# Sheet1.net
KiCad netlist of a schematic drawn in EasyEDA
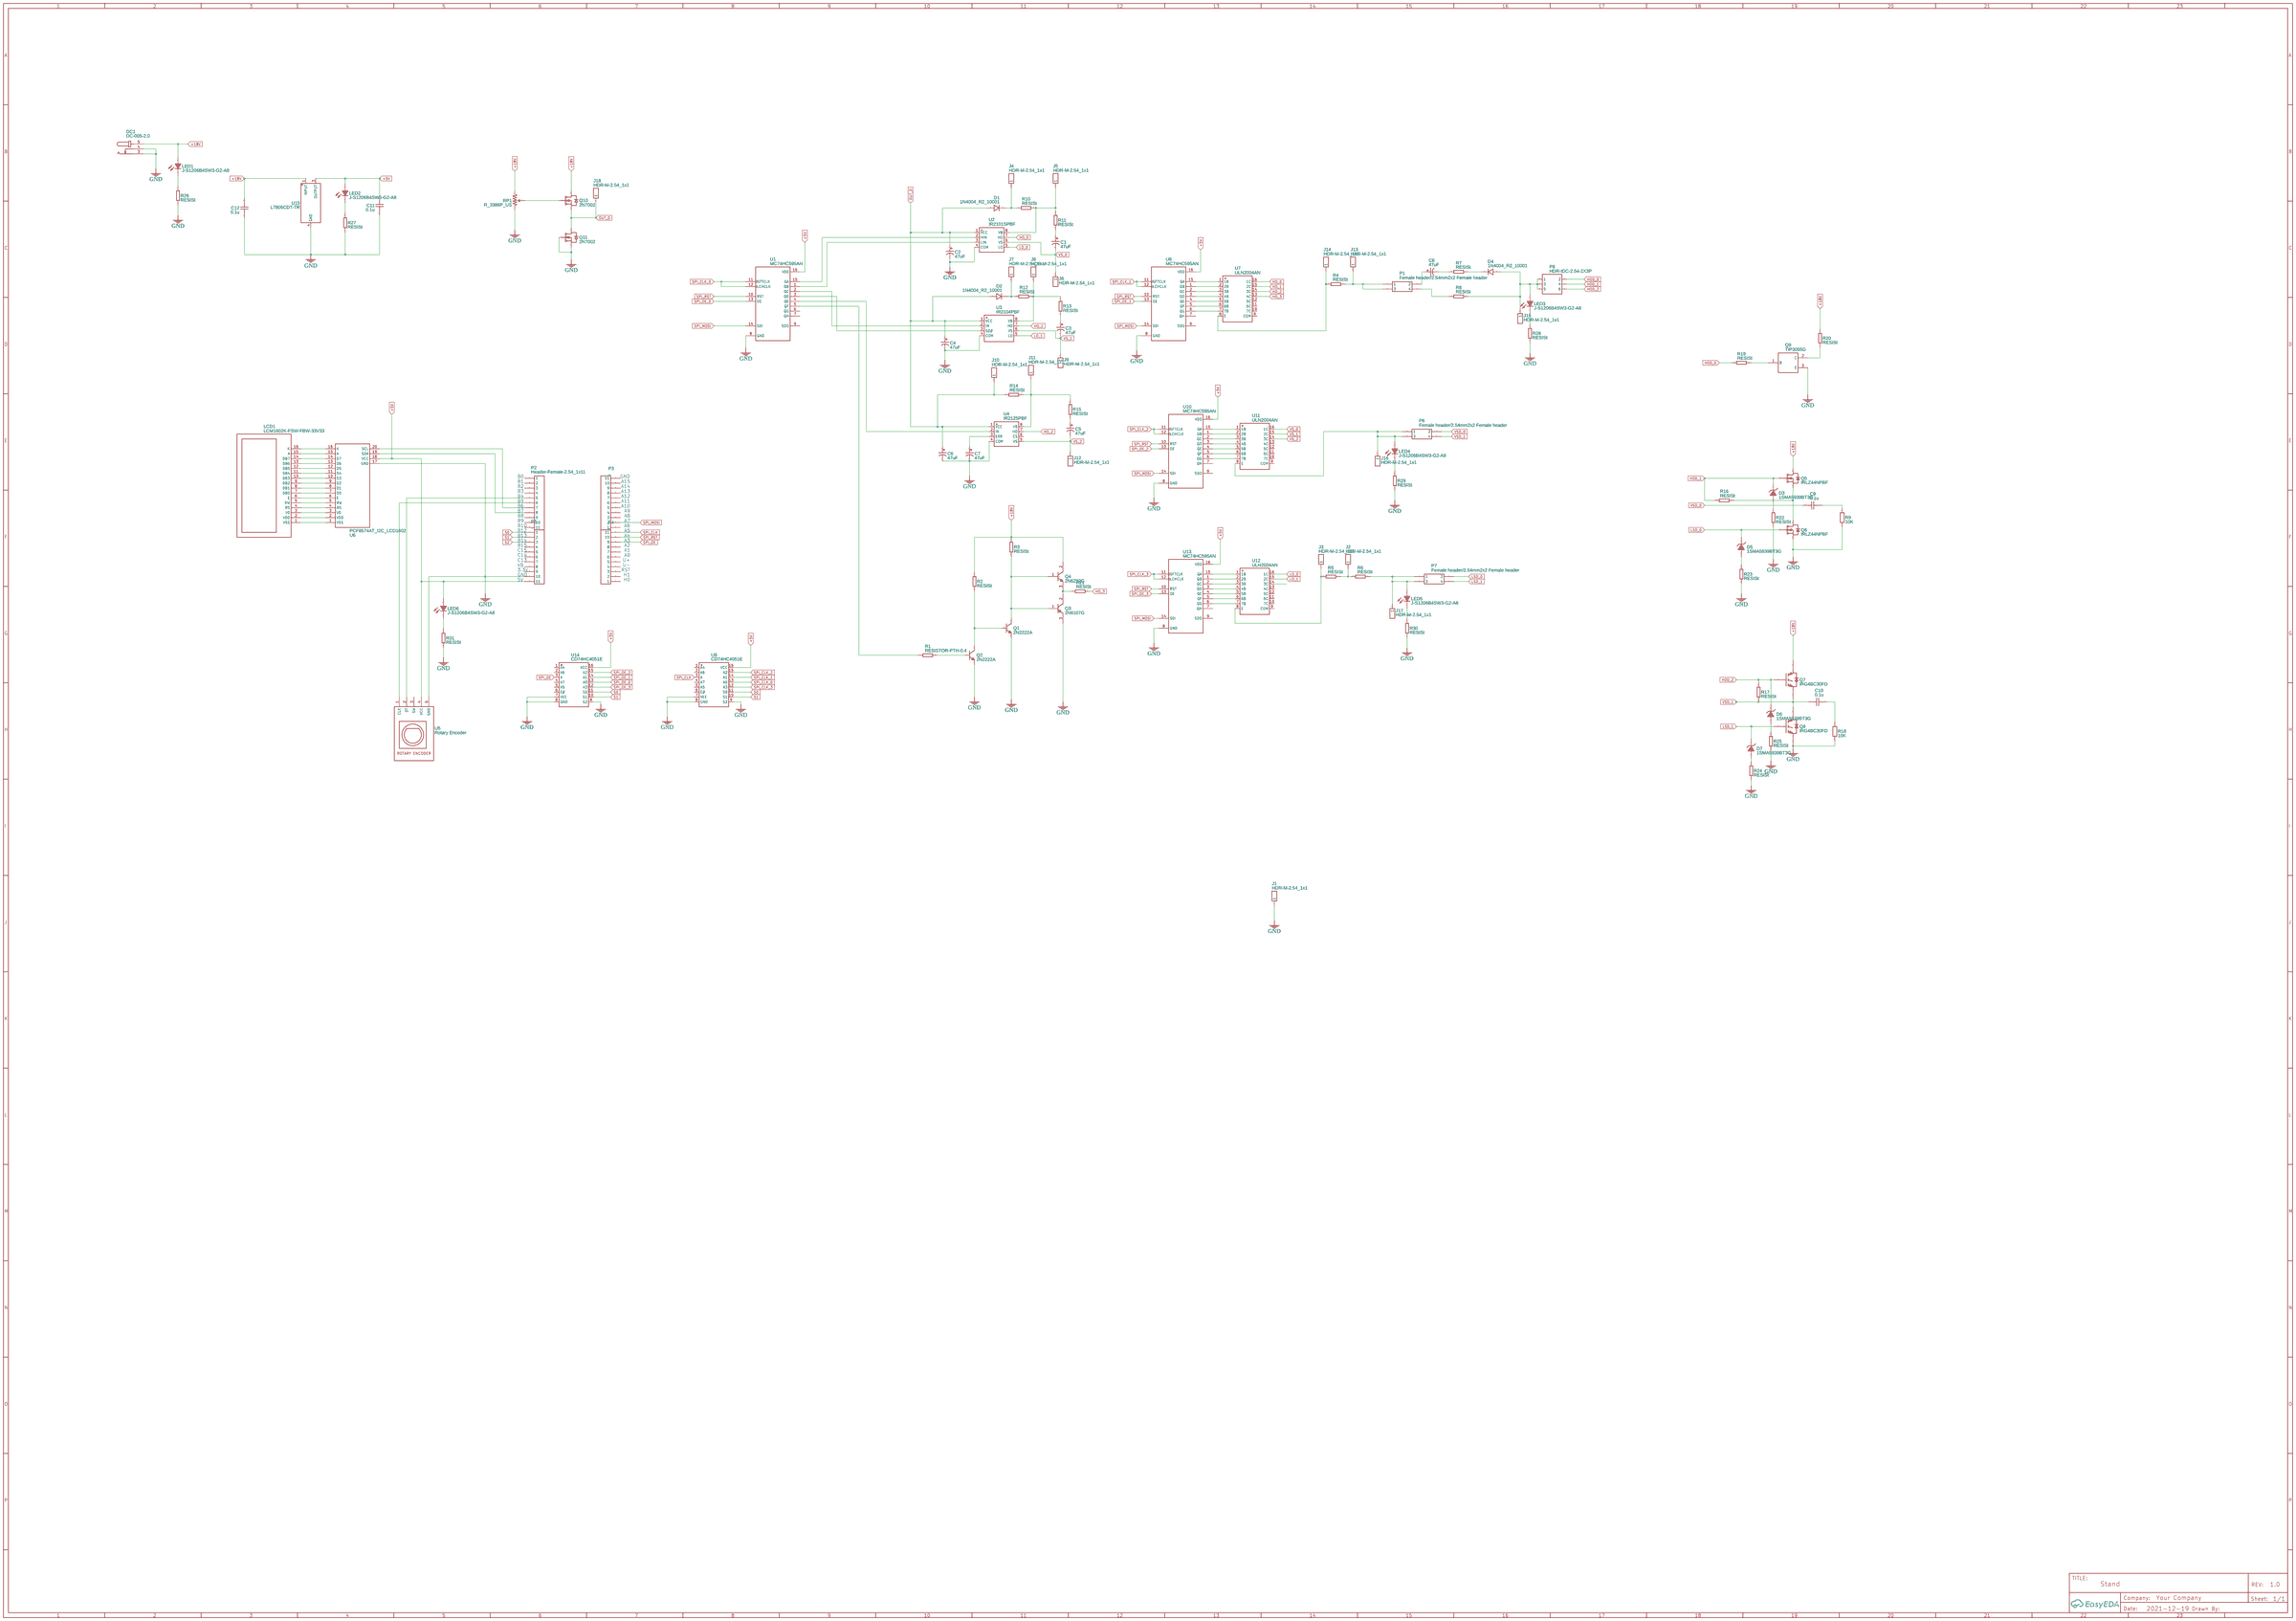
[diagram p0: schematic sheet]

(export (version "E")
  (design (tool "Eeschema 10.0.6"))
  (components
    (comp (ref "C1")
      (value "47uF")
      (fields
        (field (name "BOM_Manufacturer Part") "RD1J476M6L011PC380")
        (field (name "BOM_Supplier Part") "C238012")
      )
      (libsource (lib "") (part "RD1J476M6L011PC380"))
    )
    (comp (ref "C2")
      (value "47uF")
      (fields
        (field (name "BOM_Manufacturer Part") "RD1J476M6L011PC380")
        (field (name "BOM_Supplier Part") "C238012")
      )
      (libsource (lib "") (part "RD1J476M6L011PC380"))
    )
    (comp (ref "C3")
      (value "47uF")
      (fields
        (field (name "BOM_Manufacturer Part") "RD1J476M6L011PC380")
        (field (name "BOM_Supplier Part") "C238012")
      )
      (libsource (lib "") (part "RD1J476M6L011PC380"))
    )
    (comp (ref "C4")
      (value "47uF")
      (fields
        (field (name "BOM_Manufacturer Part") "RD1J476M6L011PC380")
        (field (name "BOM_Supplier Part") "C238012")
      )
      (libsource (lib "") (part "RD1J476M6L011PC380"))
    )
    (comp (ref "C5")
      (value "47uF")
      (fields
        (field (name "BOM_Manufacturer Part") "RD1J476M6L011PC380")
        (field (name "BOM_Supplier Part") "C238012")
      )
      (libsource (lib "") (part "RD1J476M6L011PC380"))
    )
    (comp (ref "C6")
      (value "47uF")
      (fields
        (field (name "BOM_Manufacturer Part") "RD1J476M6L011PC380")
        (field (name "BOM_Supplier Part") "C238012")
      )
      (libsource (lib "") (part "RD1J476M6L011PC380"))
    )
    (comp (ref "C7")
      (value "47uF")
      (fields
        (field (name "BOM_Manufacturer Part") "RD1J476M6L011PC380")
        (field (name "BOM_Supplier Part") "C238012")
      )
      (libsource (lib "") (part "RD1J476M6L011PC380"))
    )
    (comp (ref "C8")
      (value "47uF")
      (fields
        (field (name "BOM_Manufacturer Part") "RD1J476M6L011PC380")
        (field (name "BOM_Supplier Part") "C238012")
      )
      (libsource (lib "") (part "RD1J476M6L011PC380_1"))
    )
    (comp (ref "C9") (value "0.1u") (libsource (lib "") (part "C_0603_US")))
    (comp (ref "C10") (value "0.1u") (libsource (lib "") (part "C_0603_US")))
    (comp (ref "C11") (value "0.1u") (libsource (lib "") (part "C_0603_US_1")))
    (comp (ref "C12") (value "0.1u") (libsource (lib "") (part "C_0603_US_1")))
    (comp (ref "D1")
      (value "1N4004_R2_10001")
      (fields (field (name "BOM_Supplier Part") "C391322"))
      (libsource (lib "") (part "1N4004_R2_10001_1"))
    )
    (comp (ref "D2")
      (value "1N4004_R2_10001")
      (fields (field (name "BOM_Supplier Part") "C391322"))
      (libsource (lib "") (part "1N4004_R2_10001_1"))
    )
    (comp (ref "D3")
      (value "1SMA5939BT3G")
      (fields (field (name "BOM_Supplier Part") "C238874"))
      (libsource (lib "") (part "1SMA5939BT3G"))
    )
    (comp (ref "D4")
      (value "1N4004_R2_10001")
      (fields (field (name "BOM_Supplier Part") "C391322"))
      (libsource (lib "") (part "1N4004_R2_10001"))
    )
    (comp (ref "D5")
      (value "1SMA5939BT3G")
      (fields (field (name "BOM_Supplier Part") "C238874"))
      (libsource (lib "") (part "1SMA5939BT3G"))
    )
    (comp (ref "D6")
      (value "1SMA5939BT3G")
      (fields (field (name "BOM_Supplier Part") "C238874"))
      (libsource (lib "") (part "1SMA5939BT3G"))
    )
    (comp (ref "D7")
      (value "1SMA5939BT3G")
      (fields (field (name "BOM_Supplier Part") "C238874"))
      (libsource (lib "") (part "1SMA5939BT3G"))
    )
    (comp (ref "DC1")
      (value "DC-005-2.0")
      (fields (field (name "BOM_Supplier Part") "C521451"))
      (libsource (lib "") (part "DC-005-2.0"))
    )
    (comp (ref "J1")
      (value "HDR-M-2.54_1x1")
      (fields (field (name "BOM_Supplier Part") "C81276"))
      (libsource (lib "") (part "HDR-M-2.54_1x1"))
    )
    (comp (ref "J2")
      (value "HDR-M-2.54_1x1")
      (fields (field (name "BOM_Supplier Part") "C81276"))
      (libsource (lib "") (part "HDR-M-2.54_1x1"))
    )
    (comp (ref "J3")
      (value "HDR-M-2.54_1x1")
      (fields (field (name "BOM_Supplier Part") "C81276"))
      (libsource (lib "") (part "HDR-M-2.54_1x1"))
    )
    (comp (ref "J4")
      (value "HDR-M-2.54_1x1")
      (fields (field (name "BOM_Supplier Part") "C81276"))
      (libsource (lib "") (part "HDR-M-2.54_1x1"))
    )
    (comp (ref "J5")
      (value "HDR-M-2.54_1x1")
      (fields (field (name "BOM_Supplier Part") "C81276"))
      (libsource (lib "") (part "HDR-M-2.54_1x1"))
    )
    (comp (ref "J6")
      (value "HDR-M-2.54_1x1")
      (fields (field (name "BOM_Supplier Part") "C81276"))
      (libsource (lib "") (part "HDR-M-2.54_1x1_1"))
    )
    (comp (ref "J7")
      (value "HDR-M-2.54_1x1")
      (fields (field (name "BOM_Supplier Part") "C81276"))
      (libsource (lib "") (part "HDR-M-2.54_1x1"))
    )
    (comp (ref "J8")
      (value "HDR-M-2.54_1x1")
      (fields (field (name "BOM_Supplier Part") "C81276"))
      (libsource (lib "") (part "HDR-M-2.54_1x1"))
    )
    (comp (ref "J9")
      (value "HDR-M-2.54_1x1")
      (fields (field (name "BOM_Supplier Part") "C81276"))
      (libsource (lib "") (part "HDR-M-2.54_1x1_1"))
    )
    (comp (ref "J10")
      (value "HDR-M-2.54_1x1")
      (fields (field (name "BOM_Supplier Part") "C81276"))
      (libsource (lib "") (part "HDR-M-2.54_1x1"))
    )
    (comp (ref "J11")
      (value "HDR-M-2.54_1x1")
      (fields (field (name "BOM_Supplier Part") "C81276"))
      (libsource (lib "") (part "HDR-M-2.54_1x1"))
    )
    (comp (ref "J12")
      (value "HDR-M-2.54_1x1")
      (fields (field (name "BOM_Supplier Part") "C81276"))
      (libsource (lib "") (part "HDR-M-2.54_1x1_1"))
    )
    (comp (ref "J13")
      (value "HDR-M-2.54_1x1")
      (fields (field (name "BOM_Supplier Part") "C81276"))
      (libsource (lib "") (part "HDR-M-2.54_1x1"))
    )
    (comp (ref "J14")
      (value "HDR-M-2.54_1x1")
      (fields (field (name "BOM_Supplier Part") "C81276"))
      (libsource (lib "") (part "HDR-M-2.54_1x1"))
    )
    (comp (ref "J15")
      (value "HDR-M-2.54_1x1")
      (fields (field (name "BOM_Supplier Part") "C81276"))
      (libsource (lib "") (part "HDR-M-2.54_1x1_1"))
    )
    (comp (ref "J16")
      (value "HDR-M-2.54_1x1")
      (fields (field (name "BOM_Supplier Part") "C81276"))
      (libsource (lib "") (part "HDR-M-2.54_1x1_1"))
    )
    (comp (ref "J17")
      (value "HDR-M-2.54_1x1")
      (fields (field (name "BOM_Supplier Part") "C81276"))
      (libsource (lib "") (part "HDR-M-2.54_1x1_1"))
    )
    (comp (ref "J18")
      (value "HDR-M-2.54_1x1")
      (fields (field (name "BOM_Supplier Part") "C81276"))
      (libsource (lib "") (part "HDR-M-2.54_1x1"))
    )
    (comp (ref "LCD1")
      (value "LCM1602K-FSW-FBW-33V33")
      (fields (field (name "BOM_Supplier Part") "C83271"))
      (libsource (lib "") (part "LCM1602K-FSW-FBW-33V33"))
    )
    (comp (ref "LED1")
      (value "J-S1206B4SW3-G2-A8")
      (fields (field (name "BOM_Supplier Part") "C2917491"))
      (libsource (lib "") (part "J-S1206B4SW3-G2-A8"))
    )
    (comp (ref "LED2")
      (value "J-S1206B4SW3-G2-A8")
      (fields (field (name "BOM_Supplier Part") "C2917491"))
      (libsource (lib "") (part "J-S1206B4SW3-G2-A8"))
    )
    (comp (ref "LED3")
      (value "J-S1206B4SW3-G2-A8")
      (fields (field (name "BOM_Supplier Part") "C2917491"))
      (libsource (lib "") (part "J-S1206B4SW3-G2-A8"))
    )
    (comp (ref "LED4")
      (value "J-S1206B4SW3-G2-A8")
      (fields (field (name "BOM_Supplier Part") "C2917491"))
      (libsource (lib "") (part "J-S1206B4SW3-G2-A8"))
    )
    (comp (ref "LED5")
      (value "J-S1206B4SW3-G2-A8")
      (fields (field (name "BOM_Supplier Part") "C2917491"))
      (libsource (lib "") (part "J-S1206B4SW3-G2-A8"))
    )
    (comp (ref "LED6")
      (value "J-S1206B4SW3-G2-A8")
      (fields (field (name "BOM_Supplier Part") "C2917491"))
      (libsource (lib "") (part "J-S1206B4SW3-G2-A8"))
    )
    (comp (ref "P1")
      (value "Female header/2.54mm2x2 Female header")
      (fields (field (name "BOM_Supplier Part") "undefined"))
      (libsource (lib "") (part "Female header/2.54mm2x2 Female header"))
    )
    (comp (ref "P2")
      (value "Header-Female-2.54_1x11")
      (fields
        (field (name "BOM_Manufacturer Part") "Header-Female-2.54_1x10")
        (field (name "BOM_Supplier Part") "undefined")
      )
      (libsource (lib "") (part "Header-Female-2.54_1x11"))
    )
    (comp (ref "P3")
      (value "_")
      (fields
        (field (name "BOM_Manufacturer Part") "Header-Female-2.54_1x10")
        (field (name "BOM_Supplier Part") "undefined")
      )
      (libsource (lib "") (part "Header-Female-2.54_1x11_1"))
    )
    (comp (ref "P4")
      (value "_")
      (fields
        (field (name "BOM_Manufacturer Part") "Header-Female-2.54_1x10")
        (field (name "BOM_Supplier Part") "undefined")
      )
      (libsource (lib "") (part "Header-Female-2.54_1x11_1"))
    )
    (comp (ref "P5")
      (value "_")
      (fields
        (field (name "BOM_Manufacturer Part") "Header-Female-2.54_1x10")
        (field (name "BOM_Supplier Part") "undefined")
      )
      (libsource (lib "") (part "Header-Female-2.54_1x11"))
    )
    (comp (ref "P6")
      (value "Female header/2.54mm2x2 Female header")
      (fields (field (name "BOM_Supplier Part") "undefined"))
      (libsource (lib "") (part "Female header/2.54mm2x2 Female header"))
    )
    (comp (ref "P7")
      (value "Female header/2.54mm2x2 Female header")
      (fields (field (name "BOM_Supplier Part") "undefined"))
      (libsource (lib "") (part "Female header/2.54mm2x2 Female header"))
    )
    (comp (ref "P8")
      (value "HDR-IDC-2.54-2X3P")
      (fields
        (field (name "BOM_Manufacturer Part") "2X3 2.54mm IDC Box")
        (field (name "BOM_Supplier Part") "C11214")
      )
      (libsource (lib "") (part "HDR-IDC-2.54-2X3P"))
    )
    (comp (ref "Q1")
      (value "2N2222A")
      (fields (field (name "BOM_Supplier Part") "C358533"))
      (libsource (lib "") (part "2N2222A"))
    )
    (comp (ref "Q2")
      (value "2N2222A")
      (fields (field (name "BOM_Supplier Part") "C358533"))
      (libsource (lib "") (part "2N2222A"))
    )
    (comp (ref "Q3") (value "2N6107G") (libsource (lib "") (part "2N6107G")))
    (comp (ref "Q4") (value "2N6292G") (libsource (lib "") (part "2N6292G")))
    (comp (ref "Q5")
      (value "IRLZ44NPBF")
      (fields (field (name "BOM_Supplier Part") "C38774"))
      (libsource (lib "") (part "IRLZ44NPBF"))
    )
    (comp (ref "Q6")
      (value "IRLZ44NPBF")
      (fields (field (name "BOM_Supplier Part") "C38774"))
      (libsource (lib "") (part "IRLZ44NPBF"))
    )
    (comp (ref "Q7") (value "IRG4BC30FD") (libsource (lib "") (part "IRG4BC30FD")))
    (comp (ref "Q8") (value "IRG4BC30FD") (libsource (lib "") (part "IRG4BC30FD")))
    (comp (ref "Q9") (value "TIP3055G") (libsource (lib "") (part "TIP3055G")))
    (comp (ref "Q10")
      (value "2N7002")
      (fields (field (name "BOM_Manufacturer Part") "2N7002,215") (field (name "BOM_Supplier Part") "C65189"))
      (libsource (lib "") (part "2N7002"))
    )
    (comp (ref "Q11")
      (value "2N7002")
      (fields (field (name "BOM_Manufacturer Part") "2N7002,215") (field (name "BOM_Supplier Part") "C65189"))
      (libsource (lib "") (part "2N7002"))
    )
    (comp (ref "R1") (value "RESISTOR-PTH-0.4") (libsource (lib "") (part "RESISTOR-PTH-0.4_2")))
    (comp (ref "R2") (value "RESISt") (libsource (lib "") (part "RESISTOR-PTH-0.4")))
    (comp (ref "R3") (value "RESISt") (libsource (lib "") (part "RESISTOR-PTH-0.4")))
    (comp (ref "R4") (value "RESISt") (libsource (lib "") (part "RESISTOR-PTH-0.4_3")))
    (comp (ref "R5") (value "RESISt") (libsource (lib "") (part "RESISTOR-PTH-0.4_3")))
    (comp (ref "R6") (value "RESISt") (libsource (lib "") (part "RESISTOR-PTH-0.4_3")))
    (comp (ref "R7") (value "RESISt") (libsource (lib "") (part "RESISTOR-PTH-0.4_3")))
    (comp (ref "R8") (value "RESISt") (libsource (lib "") (part "RESISTOR-PTH-0.4_3")))
    (comp (ref "R9")
      (value "10K")
      (fields
        (field (name "BOM_Manufacturer Part") "EWWR0010J10K0T9")
        (field (name "BOM_Supplier Part") "C349083")
      )
      (libsource (lib "") (part "EWWR0010J10K0T9"))
    )
    (comp (ref "R10") (value "RESISt") (libsource (lib "") (part "RESISTOR-PTH-0.4_2")))
    (comp (ref "R11") (value "RESISt") (libsource (lib "") (part "RESISTOR-PTH-0.4")))
    (comp (ref "R12") (value "RESISt") (libsource (lib "") (part "RESISTOR-PTH-0.4_2")))
    (comp (ref "R13") (value "RESISt") (libsource (lib "") (part "RESISTOR-PTH-0.4_1")))
    (comp (ref "R14") (value "RESISt") (libsource (lib "") (part "RESISTOR-PTH-0.4_2")))
    (comp (ref "R15") (value "RESISt") (libsource (lib "") (part "RESISTOR-PTH-0.4_1")))
    (comp (ref "R16") (value "RESISt") (libsource (lib "") (part "RESISTOR-PTH-0.4_3")))
    (comp (ref "R17") (value "RESISt") (libsource (lib "") (part "RESISTOR-PTH-0.4_1")))
    (comp (ref "R18")
      (value "10K")
      (fields
        (field (name "BOM_Manufacturer Part") "EWWR0010J10K0T9")
        (field (name "BOM_Supplier Part") "C349083")
      )
      (libsource (lib "") (part "EWWR0010J10K0T9"))
    )
    (comp (ref "R19") (value "RESISt") (libsource (lib "") (part "RESISTOR-PTH-0.4_3")))
    (comp (ref "R20") (value "RESISt") (libsource (lib "") (part "RESISTOR-PTH-0.4_1")))
    (comp (ref "R21") (value "RESISt") (libsource (lib "") (part "RESISTOR-PTH-0.4_2")))
    (comp (ref "R22") (value "RESISt") (libsource (lib "") (part "RESISTOR-PTH-0.4_1")))
    (comp (ref "R23") (value "RESISt") (libsource (lib "") (part "RESISTOR-PTH-0.4_1")))
    (comp (ref "R24") (value "RESISt") (libsource (lib "") (part "RESISTOR-PTH-0.4_1")))
    (comp (ref "R25") (value "RESISt") (libsource (lib "") (part "RESISTOR-PTH-0.4_1")))
    (comp (ref "R26") (value "RESISt") (libsource (lib "") (part "RESISTOR-PTH-0.4_1")))
    (comp (ref "R27") (value "RESISt") (libsource (lib "") (part "RESISTOR-PTH-0.4_1")))
    (comp (ref "R28") (value "RESISt") (libsource (lib "") (part "RESISTOR-PTH-0.4_1")))
    (comp (ref "R29") (value "RESISt") (libsource (lib "") (part "RESISTOR-PTH-0.4_1")))
    (comp (ref "R30") (value "RESISt") (libsource (lib "") (part "RESISTOR-PTH-0.4_1")))
    (comp (ref "R31") (value "RESISt") (libsource (lib "") (part "RESISTOR-PTH-0.4_1")))
    (comp (ref "RP1") (value "R_3386P_US") (libsource (lib "") (part "R_3386P_US")))
    (comp (ref "U1") (value "MC74HC595AN") (libsource (lib "") (part "MC74HC595AN")))
    (comp (ref "U2")
      (value "IR2101SPBF")
      (fields (field (name "BOM_Supplier Part") "C537541"))
      (libsource (lib "") (part "IR2101SPBF"))
    )
    (comp (ref "U3")
      (value "IR2104PBF")
      (fields (field (name "BOM_Supplier Part") "C2959"))
      (libsource (lib "") (part "IR2104PBF"))
    )
    (comp (ref "U4")
      (value "IR2125PBF")
      (fields (field (name "BOM_Supplier Part") "C537562"))
      (libsource (lib "") (part "IR2125PBF"))
    )
    (comp (ref "U5")
      (value "Rotary Encoder")
      (fields (field (name "BOM_Manufacturer Part") "KY-040"))
      (libsource (lib "") (part "Rotary Encoder"))
    )
    (comp (ref "U6")
      (value "PCF8574AT_I2C_LCD1602")
      (fields (field (name "BOM_Manufacturer Part") "PCF8574AT_modul"))
      (libsource (lib "") (part "PCF8574AT_I2C_LCD1602"))
    )
    (comp (ref "U7")
      (value "ULN2004AN")
      (fields (field (name "BOM_Supplier Part") "C17226"))
      (libsource (lib "") (part "ULN2004AN"))
    )
    (comp (ref "U8") (value "MC74HC595AN") (libsource (lib "") (part "MC74HC595AN")))
    (comp (ref "U9")
      (value "CD74HC4051E")
      (fields (field (name "BOM_Supplier Part") "C205976"))
      (libsource (lib "") (part "CD74HC4051E"))
    )
    (comp (ref "U10") (value "MC74HC595AN") (libsource (lib "") (part "MC74HC595AN")))
    (comp (ref "U11")
      (value "ULN2004AN")
      (fields (field (name "BOM_Supplier Part") "C17226"))
      (libsource (lib "") (part "ULN2004AN"))
    )
    (comp (ref "U12")
      (value "ULN2004AN")
      (fields (field (name "BOM_Supplier Part") "C17226"))
      (libsource (lib "") (part "ULN2004AN"))
    )
    (comp (ref "U13") (value "MC74HC595AN") (libsource (lib "") (part "MC74HC595AN")))
    (comp (ref "U14")
      (value "CD74HC4051E")
      (fields (field (name "BOM_Supplier Part") "C205976"))
      (libsource (lib "") (part "CD74HC4051E"))
    )
    (comp (ref "U15")
      (value "L7805CDT-TR")
      (fields (field (name "BOM_Supplier Part") "C310413"))
      (libsource (lib "") (part "L7805CDT-TR"))
    )
  )
  (nets
    (net (code "1") (name "+5V") (class "Default")
      (node (ref "C11") (pin "2") (pinfunction "2_2") (pintype "unspecified"))
      (node (ref "LED2") (pin "2") (pinfunction "A_2") (pintype "input"))
      (node (ref "LED6") (pin "2") (pinfunction "A_2") (pintype "input"))
      (node (ref "P5") (pin "11") (pinfunction "11_11") (pintype "input"))
      (node (ref "U1") (pin "16") (pinfunction "VDD_16") (pintype "passive"))
      (node (ref "U10") (pin "16") (pinfunction "VDD_16") (pintype "passive"))
      (node (ref "U13") (pin "16") (pinfunction "VDD_16") (pintype "passive"))
      (node (ref "U14") (pin "16") (pinfunction "VCC_16") (pintype "unspecified"))
      (node (ref "U15") (pin "3") (pinfunction "OUTPUT_3") (pintype "unspecified"))
      (node (ref "U5") (pin "4") (pinfunction "VCC_4") (pintype "unspecified"))
      (node (ref "U6") (pin "18") (pinfunction "VCC_18") (pintype "unspecified"))
      (node (ref "U8") (pin "16") (pinfunction "VDD_16") (pintype "passive"))
      (node (ref "U9") (pin "16") (pinfunction "VCC_16") (pintype "unspecified"))
    )
    (net (code "2") (name "+18V") (class "Default")
      (node (ref "C12") (pin "2") (pinfunction "2_2") (pintype "unspecified"))
      (node (ref "DC1") (pin "5") (pinfunction "5_5") (pintype "unspecified"))
      (node (ref "LED1") (pin "2") (pinfunction "A_2") (pintype "input"))
      (node (ref "Q10") (pin "3") (pinfunction "D_3") (pintype "unspecified"))
      (node (ref "Q4") (pin "2") (pinfunction "C_2") (pintype "unspecified"))
      (node (ref "Q5") (pin "2") (pinfunction "D_2") (pintype "unspecified"))
      (node (ref "Q7") (pin "2") (pinfunction "C_2") (pintype "unspecified"))
      (node (ref "R2") (pin "1") (pinfunction "1_1") (pintype "unspecified"))
      (node (ref "R20") (pin "2") (pinfunction "2_2") (pintype "unspecified"))
      (node (ref "R3") (pin "1") (pinfunction "1_1") (pintype "unspecified"))
      (node (ref "RP1") (pin "1") (pinfunction "1_1") (pintype "unspecified"))
      (node (ref "U15") (pin "1") (pinfunction "INPUT_1") (pintype "unspecified"))
    )
    (net (code "3") (name "GND") (class "Default")
      (node (ref "C11") (pin "1") (pinfunction "1_1") (pintype "unspecified"))
      (node (ref "C12") (pin "1") (pinfunction "1_1") (pintype "unspecified"))
      (node (ref "C2") (pin "2") (pinfunction "2_2") (pintype "input"))
      (node (ref "C4") (pin "2") (pinfunction "2_2") (pintype "input"))
      (node (ref "C6") (pin "2") (pinfunction "2_2") (pintype "input"))
      (node (ref "C7") (pin "2") (pinfunction "2_2") (pintype "input"))
      (node (ref "DC1") (pin "3") (pinfunction "3_3") (pintype "unspecified"))
      (node (ref "DC1") (pin "4") (pinfunction "4_4") (pintype "unspecified"))
      (node (ref "J1") (pin "1") (pinfunction "1_1") (pintype "input"))
      (node (ref "P5") (pin "10") (pinfunction "10_10") (pintype "input"))
      (node (ref "Q1") (pin "3") (pinfunction "E_3") (pintype "unspecified"))
      (node (ref "Q11") (pin "1") (pinfunction "G_1") (pintype "unspecified"))
      (node (ref "Q11") (pin "2") (pinfunction "S_2") (pintype "unspecified"))
      (node (ref "Q2") (pin "3") (pinfunction "E_3") (pintype "unspecified"))
      (node (ref "Q3") (pin "3") (pinfunction "E_3") (pintype "unspecified"))
      (node (ref "Q6") (pin "3") (pinfunction "S_3") (pintype "unspecified"))
      (node (ref "Q8") (pin "3") (pinfunction "E_3") (pintype "unspecified"))
      (node (ref "Q9") (pin "3") (pinfunction "E_3") (pintype "unspecified"))
      (node (ref "R18") (pin "2") (pinfunction "2_2") (pintype "unspecified"))
      (node (ref "R22") (pin "1") (pinfunction "1_1") (pintype "unspecified"))
      (node (ref "R23") (pin "1") (pinfunction "1_1") (pintype "unspecified"))
      (node (ref "R24") (pin "1") (pinfunction "1_1") (pintype "unspecified"))
      (node (ref "R25") (pin "1") (pinfunction "1_1") (pintype "unspecified"))
      (node (ref "R26") (pin "1") (pinfunction "1_1") (pintype "unspecified"))
      (node (ref "R27") (pin "1") (pinfunction "1_1") (pintype "unspecified"))
      (node (ref "R28") (pin "1") (pinfunction "1_1") (pintype "unspecified"))
      (node (ref "R29") (pin "1") (pinfunction "1_1") (pintype "unspecified"))
      (node (ref "R30") (pin "1") (pinfunction "1_1") (pintype "unspecified"))
      (node (ref "R31") (pin "1") (pinfunction "1_1") (pintype "unspecified"))
      (node (ref "R9") (pin "2") (pinfunction "2_2") (pintype "unspecified"))
      (node (ref "RP1") (pin "3") (pinfunction "3_3") (pintype "unspecified"))
      (node (ref "U1") (pin "8") (pinfunction "GND_8") (pintype "passive"))
      (node (ref "U10") (pin "8") (pinfunction "GND_8") (pintype "passive"))
      (node (ref "U13") (pin "8") (pinfunction "GND_8") (pintype "passive"))
      (node (ref "U14") (pin "7") (pinfunction "VEE_7") (pintype "unspecified"))
      (node (ref "U14") (pin "8") (pinfunction "GND_8") (pintype "unspecified"))
      (node (ref "U14") (pin "9") (pinfunction "S2_9") (pintype "unspecified"))
      (node (ref "U15") (pin "4") (pinfunction "GND_4") (pintype "unspecified"))
      (node (ref "U2") (pin "4") (pinfunction "COM_4") (pintype "unspecified"))
      (node (ref "U3") (pin "4") (pinfunction "COM_4") (pintype "unspecified"))
      (node (ref "U4") (pin "4") (pinfunction "COM_4") (pintype "unspecified"))
      (node (ref "U5") (pin "5") (pinfunction "GND_5") (pintype "unspecified"))
      (node (ref "U6") (pin "17") (pinfunction "GND_17") (pintype "unspecified"))
      (node (ref "U8") (pin "8") (pinfunction "GND_8") (pintype "passive"))
      (node (ref "U9") (pin "7") (pinfunction "VEE_7") (pintype "unspecified"))
      (node (ref "U9") (pin "8") (pinfunction "GND_8") (pintype "unspecified"))
      (node (ref "U9") (pin "9") (pinfunction "S2_9") (pintype "unspecified"))
    )
    (net (code "4") (name "HOD_0") (class "Default")
      (node (ref "P8") (pin "2") (pinfunction "2_2") (pintype "unspecified"))
      (node (ref "R19") (pin "2") (pinfunction "2_2") (pintype "unspecified"))
    )
    (net (code "5") (name "HOD_1") (class "Default")
      (node (ref "D3") (pin "1") (pinfunction "C_1") (pintype "unspecified"))
      (node (ref "P8") (pin "4") (pinfunction "4_4") (pintype "unspecified"))
      (node (ref "Q5") (pin "1") (pinfunction "G_1") (pintype "unspecified"))
      (node (ref "R16") (pin "2") (pinfunction "2_2") (pintype "unspecified"))
    )
    (net (code "6") (name "HOD_2") (class "Default")
      (node (ref "D6") (pin "1") (pinfunction "C_1") (pintype "unspecified"))
      (node (ref "P8") (pin "6") (pinfunction "6_6") (pintype "unspecified"))
      (node (ref "Q7") (pin "1") (pinfunction "G_1") (pintype "unspecified"))
      (node (ref "R17") (pin "2") (pinfunction "2_2") (pintype "unspecified"))
    )
    (net (code "7") (name "HO_0") (class "Default")
      (node (ref "U2") (pin "7") (pinfunction "HO_7") (pintype "unspecified"))
      (node (ref "U7") (pin "16") (pinfunction "1C_16") (pintype "unspecified"))
    )
    (net (code "8") (name "HO_1") (class "Default")
      (node (ref "U3") (pin "7") (pinfunction "HO_7") (pintype "unspecified"))
      (node (ref "U7") (pin "15") (pinfunction "2C_15") (pintype "unspecified"))
    )
    (net (code "9") (name "HO_2") (class "Default")
      (node (ref "U4") (pin "7") (pinfunction "HO_7") (pintype "unspecified"))
      (node (ref "U7") (pin "14") (pinfunction "3C_14") (pintype "unspecified"))
    )
    (net (code "10") (name "HO_3") (class "Default")
      (node (ref "R21") (pin "2") (pinfunction "2_2") (pintype "unspecified"))
      (node (ref "U7") (pin "13") (pinfunction "4C_13") (pintype "unspecified"))
    )
    (net (code "11") (name "LO_0") (class "Default")
      (node (ref "U12") (pin "16") (pinfunction "1C_16") (pintype "unspecified"))
      (node (ref "U2") (pin "5") (pinfunction "LO_5") (pintype "unspecified"))
    )
    (net (code "12") (name "LO_1") (class "Default")
      (node (ref "U12") (pin "15") (pinfunction "2C_15") (pintype "unspecified"))
      (node (ref "U3") (pin "5") (pinfunction "LO_5") (pintype "unspecified"))
    )
    (net (code "13") (name "LSD_0") (class "Default")
      (node (ref "D5") (pin "1") (pinfunction "C_1") (pintype "unspecified"))
      (node (ref "P7") (pin "2") (pinfunction "2_2") (pintype "input"))
      (node (ref "Q6") (pin "1") (pinfunction "G_1") (pintype "unspecified"))
    )
    (net (code "14") (name "LSD_1") (class "Default")
      (node (ref "D7") (pin "1") (pinfunction "C_1") (pintype "unspecified"))
      (node (ref "P7") (pin "4") (pinfunction "4_4") (pintype "input"))
      (node (ref "Q8") (pin "1") (pinfunction "G_1") (pintype "unspecified"))
    )
    (net (code "15") (name "Net-(C1-Pad1)") (class "Default")
      (node (ref "C1") (pin "1") (pinfunction "1_1") (pintype "input"))
      (node (ref "R11") (pin "2") (pinfunction "2_2") (pintype "unspecified"))
    )
    (net (code "16") (name "Net-(C3-Pad1)") (class "Default")
      (node (ref "C3") (pin "1") (pinfunction "1_1") (pintype "input"))
      (node (ref "R13") (pin "1") (pinfunction "1_1") (pintype "unspecified"))
    )
    (net (code "17") (name "Net-(C5-Pad1)") (class "Default")
      (node (ref "C5") (pin "1") (pinfunction "1_1") (pintype "input"))
      (node (ref "R15") (pin "1") (pinfunction "1_1") (pintype "unspecified"))
    )
    (net (code "18") (name "Net-(C8-Pad1)") (class "Default")
      (node (ref "C8") (pin "1") (pinfunction "1_1") (pintype "input"))
      (node (ref "P1") (pin "2") (pinfunction "2_2") (pintype "input"))
    )
    (net (code "19") (name "Net-(C8-Pad2)") (class "Default")
      (node (ref "C8") (pin "2") (pinfunction "2_2") (pintype "input"))
      (node (ref "R7") (pin "2") (pinfunction "2_2") (pintype "unspecified"))
    )
    (net (code "20") (name "Net-(C9-Pad2)") (class "Default")
      (node (ref "C9") (pin "2") (pinfunction "2_2") (pintype "unspecified"))
      (node (ref "R9") (pin "1") (pinfunction "1_1") (pintype "unspecified"))
    )
    (net (code "21") (name "Net-(C10-Pad2)") (class "Default")
      (node (ref "C10") (pin "2") (pinfunction "2_2") (pintype "unspecified"))
      (node (ref "R18") (pin "1") (pinfunction "1_1") (pintype "unspecified"))
    )
    (net (code "22") (name "Net-(D1-C)") (class "Default")
      (node (ref "D1") (pin "1") (pinfunction "C_1") (pintype "unspecified"))
      (node (ref "J4") (pin "1") (pinfunction "1_1") (pintype "input"))
      (node (ref "R10") (pin "1") (pinfunction "1_1") (pintype "unspecified"))
    )
    (net (code "23") (name "Net-(D2-C)") (class "Default")
      (node (ref "D2") (pin "1") (pinfunction "C_1") (pintype "unspecified"))
      (node (ref "J7") (pin "1") (pinfunction "1_1") (pintype "input"))
      (node (ref "R12") (pin "1") (pinfunction "1_1") (pintype "unspecified"))
    )
    (net (code "24") (name "Net-(D3-A)") (class "Default")
      (node (ref "D3") (pin "2") (pinfunction "A_2") (pintype "unspecified"))
      (node (ref "R22") (pin "2") (pinfunction "2_2") (pintype "unspecified"))
    )
    (net (code "25") (name "Net-(D4-A)") (class "Default")
      (node (ref "D4") (pin "2") (pinfunction "A_2") (pintype "unspecified"))
      (node (ref "J15") (pin "1") (pinfunction "1_1") (pintype "input"))
      (node (ref "LED3") (pin "2") (pinfunction "A_2") (pintype "input"))
      (node (ref "P8") (pin "1") (pinfunction "1_1") (pintype "unspecified"))
      (node (ref "P8") (pin "3") (pinfunction "3_3") (pintype "unspecified"))
      (node (ref "P8") (pin "5") (pinfunction "5_5") (pintype "unspecified"))
      (node (ref "R8") (pin "1") (pinfunction "1_1") (pintype "unspecified"))
    )
    (net (code "26") (name "Net-(D4-C)") (class "Default")
      (node (ref "D4") (pin "1") (pinfunction "C_1") (pintype "unspecified"))
      (node (ref "R7") (pin "1") (pinfunction "1_1") (pintype "unspecified"))
    )
    (net (code "27") (name "Net-(D5-A)") (class "Default")
      (node (ref "D5") (pin "2") (pinfunction "A_2") (pintype "unspecified"))
      (node (ref "R23") (pin "2") (pinfunction "2_2") (pintype "unspecified"))
    )
    (net (code "28") (name "Net-(D6-A)") (class "Default")
      (node (ref "D6") (pin "2") (pinfunction "A_2") (pintype "unspecified"))
      (node (ref "R25") (pin "2") (pinfunction "2_2") (pintype "unspecified"))
    )
    (net (code "29") (name "Net-(D7-A)") (class "Default")
      (node (ref "D7") (pin "2") (pinfunction "A_2") (pintype "unspecified"))
      (node (ref "R24") (pin "2") (pinfunction "2_2") (pintype "unspecified"))
    )
    (net (code "30") (name "Net-(J2-Pad1)") (class "Default")
      (node (ref "J2") (pin "1") (pinfunction "1_1") (pintype "input"))
      (node (ref "R5") (pin "1") (pinfunction "1_1") (pintype "unspecified"))
      (node (ref "R6") (pin "2") (pinfunction "2_2") (pintype "unspecified"))
    )
    (net (code "31") (name "Net-(J13-Pad1)") (class "Default")
      (node (ref "J13") (pin "1") (pinfunction "1_1") (pintype "input"))
      (node (ref "P1") (pin "1") (pinfunction "1_1") (pintype "input"))
      (node (ref "P1") (pin "3") (pinfunction "3_3") (pintype "input"))
      (node (ref "R4") (pin "1") (pinfunction "1_1") (pintype "unspecified"))
    )
    (net (code "32") (name "Net-(LCD1-A)") (class "Default")
      (node (ref "LCD1") (pin "15") (pinfunction "A_15") (pintype "unspecified"))
      (node (ref "U6") (pin "15") (pinfunction "A_15") (pintype "unspecified"))
    )
    (net (code "33") (name "Net-(LCD1-DB0)") (class "Default")
      (node (ref "LCD1") (pin "7") (pinfunction "DB0_7") (pintype "unspecified"))
      (node (ref "U6") (pin "7") (pinfunction "D0_7") (pintype "unspecified"))
    )
    (net (code "34") (name "Net-(LCD1-DB1)") (class "Default")
      (node (ref "LCD1") (pin "8") (pinfunction "DB1_8") (pintype "unspecified"))
      (node (ref "U6") (pin "8") (pinfunction "D1_8") (pintype "unspecified"))
    )
    (net (code "35") (name "Net-(LCD1-DB2)") (class "Default")
      (node (ref "LCD1") (pin "9") (pinfunction "DB2_9") (pintype "unspecified"))
      (node (ref "U6") (pin "9") (pinfunction "D2_9") (pintype "unspecified"))
    )
    (net (code "36") (name "Net-(LCD1-DB3)") (class "Default")
      (node (ref "LCD1") (pin "10") (pinfunction "DB3_10") (pintype "unspecified"))
      (node (ref "U6") (pin "10") (pinfunction "D3_10") (pintype "unspecified"))
    )
    (net (code "37") (name "Net-(LCD1-DB4)") (class "Default")
      (node (ref "LCD1") (pin "11") (pinfunction "DB4_11") (pintype "unspecified"))
      (node (ref "U6") (pin "11") (pinfunction "D4_11") (pintype "unspecified"))
    )
    (net (code "38") (name "Net-(LCD1-DB5)") (class "Default")
      (node (ref "LCD1") (pin "12") (pinfunction "DB5_12") (pintype "unspecified"))
      (node (ref "U6") (pin "12") (pinfunction "D5_12") (pintype "unspecified"))
    )
    (net (code "39") (name "Net-(LCD1-DB6)") (class "Default")
      (node (ref "LCD1") (pin "13") (pinfunction "DB6_13") (pintype "unspecified"))
      (node (ref "U6") (pin "13") (pinfunction "D6_13") (pintype "unspecified"))
    )
    (net (code "40") (name "Net-(LCD1-DB7)") (class "Default")
      (node (ref "LCD1") (pin "14") (pinfunction "DB7_14") (pintype "unspecified"))
      (node (ref "U6") (pin "14") (pinfunction "D7_14") (pintype "unspecified"))
    )
    (net (code "41") (name "Net-(LCD1-E)") (class "Default")
      (node (ref "LCD1") (pin "6") (pinfunction "E_6") (pintype "unspecified"))
      (node (ref "U6") (pin "6") (pinfunction "E_6") (pintype "unspecified"))
    )
    (net (code "42") (name "Net-(LCD1-K)") (class "Default")
      (node (ref "LCD1") (pin "16") (pinfunction "K_16") (pintype "unspecified"))
      (node (ref "U6") (pin "16") (pinfunction "K_16") (pintype "unspecified"))
    )
    (net (code "43") (name "Net-(LCD1-RS)") (class "Default")
      (node (ref "LCD1") (pin "4") (pinfunction "RS_4") (pintype "unspecified"))
      (node (ref "U6") (pin "4") (pinfunction "RS_4") (pintype "unspecified"))
    )
    (net (code "44") (name "Net-(LCD1-RW)") (class "Default")
      (node (ref "LCD1") (pin "5") (pinfunction "RW_5") (pintype "unspecified"))
      (node (ref "U6") (pin "5") (pinfunction "RW_5") (pintype "unspecified"))
    )
    (net (code "45") (name "Net-(LCD1-V0)") (class "Default")
      (node (ref "LCD1") (pin "3") (pinfunction "V0_3") (pintype "unspecified"))
      (node (ref "U6") (pin "3") (pinfunction "V0_3") (pintype "unspecified"))
    )
    (net (code "46") (name "Net-(LCD1-VDD)") (class "Default")
      (node (ref "LCD1") (pin "2") (pinfunction "VDD_2") (pintype "unspecified"))
      (node (ref "U6") (pin "2") (pinfunction "VDD_2") (pintype "unspecified"))
    )
    (net (code "47") (name "Net-(LCD1-VSS)") (class "Default")
      (node (ref "LCD1") (pin "1") (pinfunction "VSS_1") (pintype "unspecified"))
      (node (ref "U6") (pin "1") (pinfunction "VSS_1") (pintype "unspecified"))
    )
    (net (code "48") (name "Net-(LED1-K)") (class "Default")
      (node (ref "LED1") (pin "1") (pinfunction "K_1") (pintype "input"))
      (node (ref "R26") (pin "2") (pinfunction "2_2") (pintype "unspecified"))
    )
    (net (code "49") (name "Net-(LED2-K)") (class "Default")
      (node (ref "LED2") (pin "1") (pinfunction "K_1") (pintype "input"))
      (node (ref "R27") (pin "2") (pinfunction "2_2") (pintype "unspecified"))
    )
    (net (code "50") (name "Net-(LED3-K)") (class "Default")
      (node (ref "LED3") (pin "1") (pinfunction "K_1") (pintype "input"))
      (node (ref "R28") (pin "2") (pinfunction "2_2") (pintype "unspecified"))
    )
    (net (code "51") (name "Net-(LED4-A)") (class "Default")
      (node (ref "J16") (pin "1") (pinfunction "1_1") (pintype "input"))
      (node (ref "LED4") (pin "2") (pinfunction "A_2") (pintype "input"))
      (node (ref "P6") (pin "1") (pinfunction "1_1") (pintype "input"))
      (node (ref "P6") (pin "3") (pinfunction "3_3") (pintype "input"))
      (node (ref "U11") (pin "8") (pinfunction "E_8") (pintype "unspecified"))
    )
    (net (code "52") (name "Net-(LED4-K)") (class "Default")
      (node (ref "LED4") (pin "1") (pinfunction "K_1") (pintype "input"))
      (node (ref "R29") (pin "2") (pinfunction "2_2") (pintype "unspecified"))
    )
    (net (code "53") (name "Net-(LED5-A)") (class "Default")
      (node (ref "J17") (pin "1") (pinfunction "1_1") (pintype "input"))
      (node (ref "LED5") (pin "2") (pinfunction "A_2") (pintype "input"))
      (node (ref "P7") (pin "1") (pinfunction "1_1") (pintype "input"))
      (node (ref "P7") (pin "3") (pinfunction "3_3") (pintype "input"))
      (node (ref "R6") (pin "1") (pinfunction "1_1") (pintype "unspecified"))
    )
    (net (code "54") (name "Net-(LED5-K)") (class "Default")
      (node (ref "LED5") (pin "1") (pinfunction "K_1") (pintype "input"))
      (node (ref "R30") (pin "2") (pinfunction "2_2") (pintype "unspecified"))
    )
    (net (code "55") (name "Net-(LED6-K)") (class "Default")
      (node (ref "LED6") (pin "1") (pinfunction "K_1") (pintype "input"))
      (node (ref "R31") (pin "2") (pinfunction "2_2") (pintype "unspecified"))
    )
    (net (code "56") (name "Net-(P1-Pad4)") (class "Default")
      (node (ref "P1") (pin "4") (pinfunction "4_4") (pintype "input"))
      (node (ref "R8") (pin "2") (pinfunction "2_2") (pintype "unspecified"))
    )
    (net (code "57") (name "Net-(Q1-B)") (class "Default")
      (node (ref "Q1") (pin "2") (pinfunction "B_2") (pintype "unspecified"))
      (node (ref "Q2") (pin "1") (pinfunction "C_1") (pintype "unspecified"))
      (node (ref "R2") (pin "2") (pinfunction "2_2") (pintype "unspecified"))
    )
    (net (code "58") (name "Net-(Q1-C)") (class "Default")
      (node (ref "Q1") (pin "1") (pinfunction "C_1") (pintype "unspecified"))
      (node (ref "Q3") (pin "1") (pinfunction "B_1") (pintype "unspecified"))
      (node (ref "Q4") (pin "1") (pinfunction "B_1") (pintype "unspecified"))
      (node (ref "R3") (pin "2") (pinfunction "2_2") (pintype "unspecified"))
    )
    (net (code "59") (name "Net-(Q2-B)") (class "Default")
      (node (ref "Q2") (pin "2") (pinfunction "B_2") (pintype "unspecified"))
      (node (ref "R1") (pin "2") (pinfunction "2_2") (pintype "unspecified"))
    )
    (net (code "60") (name "Net-(Q3-C)") (class "Default")
      (node (ref "Q3") (pin "2") (pinfunction "C_2") (pintype "unspecified"))
      (node (ref "Q4") (pin "3") (pinfunction "E_3") (pintype "unspecified"))
      (node (ref "R21") (pin "1") (pinfunction "1_1") (pintype "unspecified"))
    )
    (net (code "61") (name "Net-(Q5-S)") (class "Default")
      (node (ref "Q5") (pin "3") (pinfunction "S_3") (pintype "unspecified"))
      (node (ref "Q6") (pin "2") (pinfunction "D_2") (pintype "unspecified"))
      (node (ref "R16") (pin "1") (pinfunction "1_1") (pintype "unspecified"))
    )
    (net (code "62") (name "Net-(Q9-B)") (class "Default")
      (node (ref "Q9") (pin "1") (pinfunction "B_1") (pintype "unspecified"))
      (node (ref "R19") (pin "1") (pinfunction "1_1") (pintype "unspecified"))
    )
    (net (code "63") (name "Net-(Q9-C)") (class "Default")
      (node (ref "Q9") (pin "2") (pinfunction "C_2") (pintype "unspecified"))
      (node (ref "R20") (pin "1") (pinfunction "1_1") (pintype "unspecified"))
    )
    (net (code "64") (name "Net-(Q10-G)") (class "Default")
      (node (ref "Q10") (pin "1") (pinfunction "G_1") (pintype "unspecified"))
      (node (ref "RP1") (pin "2") (pinfunction "2_2") (pintype "unspecified"))
    )
    (net (code "65") (name "Net-(U1-QA)") (class "Default")
      (node (ref "U1") (pin "15") (pinfunction "QA_15") (pintype "unspecified"))
      (node (ref "U2") (pin "2") (pinfunction "HIN_2") (pintype "unspecified"))
    )
    (net (code "66") (name "Net-(U1-QB)") (class "Default")
      (node (ref "U1") (pin "1") (pinfunction "QB_1") (pintype "unspecified"))
      (node (ref "U2") (pin "3") (pinfunction "LIN_3") (pintype "unspecified"))
    )
    (net (code "67") (name "Net-(U1-QC)") (class "Default")
      (node (ref "U1") (pin "2") (pinfunction "QC_2") (pintype "unspecified"))
      (node (ref "U3") (pin "2") (pinfunction "IN_2") (pintype "unspecified"))
    )
    (net (code "68") (name "Net-(U1-QD)") (class "Default")
      (node (ref "U1") (pin "3") (pinfunction "QD_3") (pintype "unspecified"))
      (node (ref "U3") (pin "3") (pinfunction "SD#_3") (pintype "unspecified"))
    )
    (net (code "69") (name "Net-(U1-QE)") (class "Default")
      (node (ref "U1") (pin "4") (pinfunction "QE_4") (pintype "unspecified"))
      (node (ref "U4") (pin "2") (pinfunction "IN_2") (pintype "unspecified"))
    )
    (net (code "70") (name "Net-(U1-QF)") (class "Default")
      (node (ref "R1") (pin "1") (pinfunction "1_1") (pintype "unspecified"))
      (node (ref "U1") (pin "5") (pinfunction "QF_5") (pintype "unspecified"))
    )
    (net (code "71") (name "Net-(U2-VB)") (class "Default")
      (node (ref "J5") (pin "1") (pinfunction "1_1") (pintype "input"))
      (node (ref "R10") (pin "2") (pinfunction "2_2") (pintype "unspecified"))
      (node (ref "R11") (pin "1") (pinfunction "1_1") (pintype "unspecified"))
      (node (ref "U2") (pin "8") (pinfunction "VB_8") (pintype "unspecified"))
    )
    (net (code "72") (name "Net-(U3-VB)") (class "Default")
      (node (ref "J8") (pin "1") (pinfunction "1_1") (pintype "input"))
      (node (ref "R12") (pin "2") (pinfunction "2_2") (pintype "unspecified"))
      (node (ref "R13") (pin "2") (pinfunction "2_2") (pintype "unspecified"))
      (node (ref "U3") (pin "8") (pinfunction "VB_8") (pintype "unspecified"))
    )
    (net (code "73") (name "Net-(U4-ERR)") (class "Default")
      (node (ref "C7") (pin "1") (pinfunction "1_1") (pintype "input"))
      (node (ref "U4") (pin "3") (pinfunction "ERR_3") (pintype "unspecified"))
    )
    (net (code "74") (name "Net-(U4-VB)") (class "Default")
      (node (ref "J11") (pin "1") (pinfunction "1_1") (pintype "input"))
      (node (ref "R14") (pin "2") (pinfunction "2_2") (pintype "unspecified"))
      (node (ref "R15") (pin "2") (pinfunction "2_2") (pintype "unspecified"))
      (node (ref "U4") (pin "8") (pinfunction "VB_8") (pintype "unspecified"))
    )
    (net (code "75") (name "Net-(U5-CLK)") (class "Default")
      (node (ref "P2") (pin "6") (pinfunction "6_6") (pintype "input"))
      (node (ref "U5") (pin "1") (pinfunction "CLK_1") (pintype "unspecified"))
    )
    (net (code "76") (name "Net-(U5-DT)") (class "Default")
      (node (ref "P2") (pin "5") (pinfunction "5_5") (pintype "input"))
      (node (ref "U5") (pin "2") (pinfunction "DT_2") (pintype "unspecified"))
    )
    (net (code "77") (name "Net-(U6-SCL)") (class "Default")
      (node (ref "P2") (pin "7") (pinfunction "7_7") (pintype "input"))
      (node (ref "U6") (pin "20") (pinfunction "SCL_20") (pintype "unspecified"))
    )
    (net (code "78") (name "Net-(U6-SDA)") (class "Default")
      (node (ref "P2") (pin "8") (pinfunction "8_8") (pintype "input"))
      (node (ref "U6") (pin "19") (pinfunction "SDA_19") (pintype "unspecified"))
    )
    (net (code "79") (name "Net-(U7-1B)") (class "Default")
      (node (ref "U7") (pin "1") (pinfunction "1B_1") (pintype "unspecified"))
      (node (ref "U8") (pin "15") (pinfunction "QA_15") (pintype "unspecified"))
    )
    (net (code "80") (name "Net-(U7-2B)") (class "Default")
      (node (ref "U7") (pin "2") (pinfunction "2B_2") (pintype "unspecified"))
      (node (ref "U8") (pin "1") (pinfunction "QB_1") (pintype "unspecified"))
    )
    (net (code "81") (name "Net-(U7-3B)") (class "Default")
      (node (ref "U7") (pin "3") (pinfunction "3B_3") (pintype "unspecified"))
      (node (ref "U8") (pin "2") (pinfunction "QC_2") (pintype "unspecified"))
    )
    (net (code "82") (name "Net-(U7-4B)") (class "Default")
      (node (ref "U7") (pin "4") (pinfunction "4B_4") (pintype "unspecified"))
      (node (ref "U8") (pin "3") (pinfunction "QD_3") (pintype "unspecified"))
    )
    (net (code "83") (name "Net-(U7-5B)") (class "Default")
      (node (ref "U7") (pin "5") (pinfunction "5B_5") (pintype "unspecified"))
      (node (ref "U8") (pin "4") (pinfunction "QE_4") (pintype "unspecified"))
    )
    (net (code "84") (name "Net-(U7-6B)") (class "Default")
      (node (ref "U7") (pin "6") (pinfunction "6B_6") (pintype "unspecified"))
      (node (ref "U8") (pin "5") (pinfunction "QF_5") (pintype "unspecified"))
    )
    (net (code "85") (name "Net-(U7-7B)") (class "Default")
      (node (ref "U7") (pin "7") (pinfunction "7B_7") (pintype "unspecified"))
      (node (ref "U8") (pin "6") (pinfunction "QG_6") (pintype "unspecified"))
    )
    (net (code "86") (name "Net-(U7-E)") (class "Default")
      (node (ref "J14") (pin "1") (pinfunction "1_1") (pintype "input"))
      (node (ref "R4") (pin "2") (pinfunction "2_2") (pintype "unspecified"))
      (node (ref "U7") (pin "8") (pinfunction "E_8") (pintype "unspecified"))
    )
    (net (code "87") (name "Net-(U10-QA)") (class "Default")
      (node (ref "U10") (pin "15") (pinfunction "QA_15") (pintype "unspecified"))
      (node (ref "U11") (pin "1") (pinfunction "1B_1") (pintype "unspecified"))
    )
    (net (code "88") (name "Net-(U10-QB)") (class "Default")
      (node (ref "U10") (pin "1") (pinfunction "QB_1") (pintype "unspecified"))
      (node (ref "U11") (pin "2") (pinfunction "2B_2") (pintype "unspecified"))
    )
    (net (code "89") (name "Net-(U10-QC)") (class "Default")
      (node (ref "U10") (pin "2") (pinfunction "QC_2") (pintype "unspecified"))
      (node (ref "U11") (pin "3") (pinfunction "3B_3") (pintype "unspecified"))
    )
    (net (code "90") (name "Net-(U10-QD)") (class "Default")
      (node (ref "U10") (pin "3") (pinfunction "QD_3") (pintype "unspecified"))
      (node (ref "U11") (pin "4") (pinfunction "4B_4") (pintype "unspecified"))
    )
    (net (code "91") (name "Net-(U10-QE)") (class "Default")
      (node (ref "U10") (pin "4") (pinfunction "QE_4") (pintype "unspecified"))
      (node (ref "U11") (pin "5") (pinfunction "5B_5") (pintype "unspecified"))
    )
    (net (code "92") (name "Net-(U10-QF)") (class "Default")
      (node (ref "U10") (pin "5") (pinfunction "QF_5") (pintype "unspecified"))
      (node (ref "U11") (pin "6") (pinfunction "6B_6") (pintype "unspecified"))
    )
    (net (code "93") (name "Net-(U10-QG)") (class "Default")
      (node (ref "U10") (pin "6") (pinfunction "QG_6") (pintype "unspecified"))
      (node (ref "U11") (pin "7") (pinfunction "7B_7") (pintype "unspecified"))
    )
    (net (code "94") (name "Net-(U12-1B)") (class "Default")
      (node (ref "U12") (pin "1") (pinfunction "1B_1") (pintype "unspecified"))
      (node (ref "U13") (pin "15") (pinfunction "QA_15") (pintype "unspecified"))
    )
    (net (code "95") (name "Net-(U12-2B)") (class "Default")
      (node (ref "U12") (pin "2") (pinfunction "2B_2") (pintype "unspecified"))
      (node (ref "U13") (pin "1") (pinfunction "QB_1") (pintype "unspecified"))
    )
    (net (code "96") (name "Net-(U12-3B)") (class "Default")
      (node (ref "U12") (pin "3") (pinfunction "3B_3") (pintype "unspecified"))
      (node (ref "U13") (pin "2") (pinfunction "QC_2") (pintype "unspecified"))
    )
    (net (code "97") (name "Net-(U12-4B)") (class "Default")
      (node (ref "U12") (pin "4") (pinfunction "4B_4") (pintype "unspecified"))
      (node (ref "U13") (pin "3") (pinfunction "QD_3") (pintype "unspecified"))
    )
    (net (code "98") (name "Net-(U12-5B)") (class "Default")
      (node (ref "U12") (pin "5") (pinfunction "5B_5") (pintype "unspecified"))
      (node (ref "U13") (pin "4") (pinfunction "QE_4") (pintype "unspecified"))
    )
    (net (code "99") (name "Net-(U12-6B)") (class "Default")
      (node (ref "U12") (pin "6") (pinfunction "6B_6") (pintype "unspecified"))
      (node (ref "U13") (pin "5") (pinfunction "QF_5") (pintype "unspecified"))
    )
    (net (code "100") (name "Net-(U12-7B)") (class "Default")
      (node (ref "U12") (pin "7") (pinfunction "7B_7") (pintype "unspecified"))
      (node (ref "U13") (pin "6") (pinfunction "QG_6") (pintype "unspecified"))
    )
    (net (code "101") (name "Net-(U12-E)") (class "Default")
      (node (ref "J3") (pin "1") (pinfunction "1_1") (pintype "input"))
      (node (ref "R5") (pin "2") (pinfunction "2_2") (pintype "unspecified"))
      (node (ref "U12") (pin "8") (pinfunction "E_8") (pintype "unspecified"))
    )
    (net (code "102") (name "OUT_D") (class "Default")
      (node (ref "C2") (pin "1") (pinfunction "1_1") (pintype "input"))
      (node (ref "C4") (pin "1") (pinfunction "1_1") (pintype "input"))
      (node (ref "C6") (pin "1") (pinfunction "1_1") (pintype "input"))
      (node (ref "D1") (pin "2") (pinfunction "A_2") (pintype "unspecified"))
      (node (ref "D2") (pin "2") (pinfunction "A_2") (pintype "unspecified"))
      (node (ref "J10") (pin "1") (pinfunction "1_1") (pintype "input"))
      (node (ref "J18") (pin "1") (pinfunction "1_1") (pintype "input"))
      (node (ref "Q10") (pin "2") (pinfunction "S_2") (pintype "unspecified"))
      (node (ref "Q11") (pin "3") (pinfunction "D_3") (pintype "unspecified"))
      (node (ref "R14") (pin "1") (pinfunction "1_1") (pintype "unspecified"))
      (node (ref "U2") (pin "1") (pinfunction "VCC_1") (pintype "unspecified"))
      (node (ref "U3") (pin "1") (pinfunction "VCC_1") (pintype "unspecified"))
      (node (ref "U4") (pin "1") (pinfunction "VCC_1") (pintype "unspecified"))
    )
    (net (code "103") (name "S0") (class "Default")
      (node (ref "P5") (pin "1") (pinfunction "1_1") (pintype "input"))
      (node (ref "U14") (pin "11") (pinfunction "S0_11") (pintype "unspecified"))
      (node (ref "U9") (pin "11") (pinfunction "S0_11") (pintype "unspecified"))
    )
    (net (code "104") (name "S1") (class "Default")
      (node (ref "P5") (pin "2") (pinfunction "2_2") (pintype "input"))
      (node (ref "U14") (pin "10") (pinfunction "S1_10") (pintype "unspecified"))
      (node (ref "U9") (pin "10") (pinfunction "S1_10") (pintype "unspecified"))
    )
    (net (code "105") (name "S2") (class "Default")
      (node (ref "P5") (pin "3") (pinfunction "3_3") (pintype "input"))
    )
    (net (code "106") (name "SPI_CLK") (class "Default")
      (node (ref "P4") (pin "11") (pinfunction "11_11") (pintype "input"))
      (node (ref "U9") (pin "3") (pinfunction "A_3") (pintype "unspecified"))
    )
    (net (code "107") (name "SPI_CLK_0") (class "Default")
      (node (ref "U1") (pin "11") (pinfunction "SFTCLK_11") (pintype "unspecified"))
      (node (ref "U1") (pin "12") (pinfunction "LCHCLK_12") (pintype "unspecified"))
      (node (ref "U9") (pin "13") (pinfunction "A0_13") (pintype "unspecified"))
    )
    (net (code "108") (name "SPI_CLK_1") (class "Default")
      (node (ref "U8") (pin "11") (pinfunction "SFTCLK_11") (pintype "unspecified"))
      (node (ref "U8") (pin "12") (pinfunction "LCHCLK_12") (pintype "unspecified"))
      (node (ref "U9") (pin "14") (pinfunction "A1_14") (pintype "unspecified"))
    )
    (net (code "109") (name "SPI_CLK_2") (class "Default")
      (node (ref "U10") (pin "11") (pinfunction "SFTCLK_11") (pintype "unspecified"))
      (node (ref "U10") (pin "12") (pinfunction "LCHCLK_12") (pintype "unspecified"))
      (node (ref "U9") (pin "15") (pinfunction "A2_15") (pintype "unspecified"))
    )
    (net (code "110") (name "SPI_CLK_3") (class "Default")
      (node (ref "U13") (pin "11") (pinfunction "SFTCLK_11") (pintype "unspecified"))
      (node (ref "U13") (pin "12") (pinfunction "LCHCLK_12") (pintype "unspecified"))
      (node (ref "U9") (pin "12") (pinfunction "A3_12") (pintype "unspecified"))
    )
    (net (code "111") (name "SPI_MOSI") (class "Default")
      (node (ref "P3") (pin "2") (pinfunction "2_2") (pintype "input"))
      (node (ref "U1") (pin "14") (pinfunction "SDI_14") (pintype "unspecified"))
      (node (ref "U10") (pin "14") (pinfunction "SDI_14") (pintype "unspecified"))
      (node (ref "U13") (pin "14") (pinfunction "SDI_14") (pintype "unspecified"))
      (node (ref "U8") (pin "14") (pinfunction "SDI_14") (pintype "unspecified"))
    )
    (net (code "112") (name "SPI_OE") (class "Default")
      (node (ref "P4") (pin "9") (pinfunction "9_9") (pintype "input"))
      (node (ref "U14") (pin "3") (pinfunction "A_3") (pintype "unspecified"))
    )
    (net (code "113") (name "SPI_OE_0") (class "Default")
      (node (ref "U1") (pin "13") (pinfunction "OE_13") (pintype "unspecified"))
      (node (ref "U14") (pin "13") (pinfunction "A0_13") (pintype "unspecified"))
    )
    (net (code "114") (name "SPI_OE_1") (class "Default")
      (node (ref "U14") (pin "14") (pinfunction "A1_14") (pintype "unspecified"))
      (node (ref "U8") (pin "13") (pinfunction "OE_13") (pintype "unspecified"))
    )
    (net (code "115") (name "SPI_OE_2") (class "Default")
      (node (ref "U10") (pin "13") (pinfunction "OE_13") (pintype "unspecified"))
      (node (ref "U14") (pin "15") (pinfunction "A2_15") (pintype "unspecified"))
    )
    (net (code "116") (name "SPI_OE_3") (class "Default")
      (node (ref "U13") (pin "13") (pinfunction "OE_13") (pintype "unspecified"))
      (node (ref "U14") (pin "12") (pinfunction "A3_12") (pintype "unspecified"))
    )
    (net (code "117") (name "SPI_RST") (class "Default")
      (node (ref "P4") (pin "10") (pinfunction "10_10") (pintype "input"))
      (node (ref "U1") (pin "10") (pinfunction "RST_10") (pintype "unspecified"))
      (node (ref "U10") (pin "10") (pinfunction "RST_10") (pintype "unspecified"))
      (node (ref "U13") (pin "10") (pinfunction "RST_10") (pintype "unspecified"))
      (node (ref "U8") (pin "10") (pinfunction "RST_10") (pintype "unspecified"))
    )
    (net (code "118") (name "VSD_0") (class "Default")
      (node (ref "C9") (pin "1") (pinfunction "1_1") (pintype "unspecified"))
      (node (ref "P6") (pin "2") (pinfunction "2_2") (pintype "input"))
    )
    (net (code "119") (name "VSD_1") (class "Default")
      (node (ref "C10") (pin "1") (pinfunction "1_1") (pintype "unspecified"))
      (node (ref "P6") (pin "4") (pinfunction "4_4") (pintype "input"))
      (node (ref "Q7") (pin "3") (pinfunction "E_3") (pintype "unspecified"))
      (node (ref "Q8") (pin "2") (pinfunction "C_2") (pintype "unspecified"))
      (node (ref "R17") (pin "1") (pinfunction "1_1") (pintype "unspecified"))
    )
    (net (code "120") (name "VS_0") (class "Default")
      (node (ref "C1") (pin "2") (pinfunction "2_2") (pintype "input"))
      (node (ref "J6") (pin "1") (pinfunction "1_1") (pintype "input"))
      (node (ref "U11") (pin "16") (pinfunction "1C_16") (pintype "unspecified"))
      (node (ref "U2") (pin "6") (pinfunction "VS_6") (pintype "unspecified"))
    )
    (net (code "121") (name "VS_1") (class "Default")
      (node (ref "C3") (pin "2") (pinfunction "2_2") (pintype "input"))
      (node (ref "J9") (pin "1") (pinfunction "1_1") (pintype "input"))
      (node (ref "U11") (pin "15") (pinfunction "2C_15") (pintype "unspecified"))
      (node (ref "U3") (pin "6") (pinfunction "VS_6") (pintype "unspecified"))
    )
    (net (code "122") (name "VS_2") (class "Default")
      (node (ref "C5") (pin "2") (pinfunction "2_2") (pintype "input"))
      (node (ref "J12") (pin "1") (pinfunction "1_1") (pintype "input"))
      (node (ref "U11") (pin "14") (pinfunction "3C_14") (pintype "unspecified"))
      (node (ref "U4") (pin "5") (pinfunction "VS_5") (pintype "unspecified"))
    )
    (net (code "123") (name "unconnected-(P2-Pad1)") (class "Default")
      (node (ref "P2") (pin "1") (pinfunction "1_1") (pintype "input"))
    )
    (net (code "124") (name "unconnected-(P2-Pad2)") (class "Default")
      (node (ref "P2") (pin "2") (pinfunction "2_2") (pintype "input"))
    )
    (net (code "125") (name "unconnected-(P2-Pad3)") (class "Default")
      (node (ref "P2") (pin "3") (pinfunction "3_3") (pintype "input"))
    )
    (net (code "126") (name "unconnected-(P2-Pad4)") (class "Default")
      (node (ref "P2") (pin "4") (pinfunction "4_4") (pintype "input"))
    )
    (net (code "127") (name "unconnected-(P2-Pad9)") (class "Default")
      (node (ref "P2") (pin "9") (pinfunction "9_9") (pintype "input"))
    )
    (net (code "128") (name "unconnected-(P2-Pad10)") (class "Default")
      (node (ref "P2") (pin "10") (pinfunction "10_10") (pintype "input"))
    )
    (net (code "129") (name "unconnected-(P2-Pad11)") (class "Default")
      (node (ref "P2") (pin "11") (pinfunction "11_11") (pintype "input"))
    )
    (net (code "130") (name "unconnected-(P3-Pad1)") (class "Default")
      (node (ref "P3") (pin "1") (pinfunction "1_1") (pintype "input"))
    )
    (net (code "131") (name "unconnected-(P3-Pad3)") (class "Default")
      (node (ref "P3") (pin "3") (pinfunction "3_3") (pintype "input"))
    )
    (net (code "132") (name "unconnected-(P3-Pad4)") (class "Default")
      (node (ref "P3") (pin "4") (pinfunction "4_4") (pintype "input"))
    )
    (net (code "133") (name "unconnected-(P3-Pad5)") (class "Default")
      (node (ref "P3") (pin "5") (pinfunction "5_5") (pintype "input"))
    )
    (net (code "134") (name "unconnected-(P3-Pad6)") (class "Default")
      (node (ref "P3") (pin "6") (pinfunction "6_6") (pintype "input"))
    )
    (net (code "135") (name "unconnected-(P3-Pad7)") (class "Default")
      (node (ref "P3") (pin "7") (pinfunction "7_7") (pintype "input"))
    )
    (net (code "136") (name "unconnected-(P3-Pad8)") (class "Default")
      (node (ref "P3") (pin "8") (pinfunction "8_8") (pintype "input"))
    )
    (net (code "137") (name "unconnected-(P3-Pad9)") (class "Default")
      (node (ref "P3") (pin "9") (pinfunction "9_9") (pintype "input"))
    )
    (net (code "138") (name "unconnected-(P3-Pad10)") (class "Default")
      (node (ref "P3") (pin "10") (pinfunction "10_10") (pintype "input"))
    )
    (net (code "139") (name "unconnected-(P3-Pad11)") (class "Default")
      (node (ref "P3") (pin "11") (pinfunction "11_11") (pintype "input"))
    )
    (net (code "140") (name "unconnected-(P4-Pad1)") (class "Default")
      (node (ref "P4") (pin "1") (pinfunction "1_1") (pintype "input"))
    )
    (net (code "141") (name "unconnected-(P4-Pad2)") (class "Default")
      (node (ref "P4") (pin "2") (pinfunction "2_2") (pintype "input"))
    )
    (net (code "142") (name "unconnected-(P4-Pad3)") (class "Default")
      (node (ref "P4") (pin "3") (pinfunction "3_3") (pintype "input"))
    )
    (net (code "143") (name "unconnected-(P4-Pad4)") (class "Default")
      (node (ref "P4") (pin "4") (pinfunction "4_4") (pintype "input"))
    )
    (net (code "144") (name "unconnected-(P4-Pad5)") (class "Default")
      (node (ref "P4") (pin "5") (pinfunction "5_5") (pintype "input"))
    )
    (net (code "145") (name "unconnected-(P4-Pad6)") (class "Default")
      (node (ref "P4") (pin "6") (pinfunction "6_6") (pintype "input"))
    )
    (net (code "146") (name "unconnected-(P4-Pad7)") (class "Default")
      (node (ref "P4") (pin "7") (pinfunction "7_7") (pintype "input"))
    )
    (net (code "147") (name "unconnected-(P4-Pad8)") (class "Default")
      (node (ref "P4") (pin "8") (pinfunction "8_8") (pintype "input"))
    )
    (net (code "148") (name "unconnected-(P5-Pad4)") (class "Default")
      (node (ref "P5") (pin "4") (pinfunction "4_4") (pintype "input"))
    )
    (net (code "149") (name "unconnected-(P5-Pad5)") (class "Default")
      (node (ref "P5") (pin "5") (pinfunction "5_5") (pintype "input"))
    )
    (net (code "150") (name "unconnected-(P5-Pad6)") (class "Default")
      (node (ref "P5") (pin "6") (pinfunction "6_6") (pintype "input"))
    )
    (net (code "151") (name "unconnected-(P5-Pad7)") (class "Default")
      (node (ref "P5") (pin "7") (pinfunction "7_7") (pintype "input"))
    )
    (net (code "152") (name "unconnected-(P5-Pad8)") (class "Default")
      (node (ref "P5") (pin "8") (pinfunction "8_8") (pintype "input"))
    )
    (net (code "153") (name "unconnected-(P5-Pad9)") (class "Default")
      (node (ref "P5") (pin "9") (pinfunction "9_9") (pintype "input"))
    )
    (net (code "154") (name "unconnected-(U1-QG-Pad6)") (class "Default")
      (node (ref "U1") (pin "6") (pinfunction "QG_6") (pintype "unspecified"))
    )
    (net (code "155") (name "unconnected-(U1-QH-Pad7)") (class "Default")
      (node (ref "U1") (pin "7") (pinfunction "QH_7") (pintype "unspecified"))
    )
    (net (code "156") (name "unconnected-(U1-SDO-Pad9)") (class "Default")
      (node (ref "U1") (pin "9") (pinfunction "SDO_9") (pintype "output"))
    )
    (net (code "157") (name "unconnected-(U4-CS-Pad6)") (class "Default")
      (node (ref "U4") (pin "6") (pinfunction "CS_6") (pintype "unspecified"))
    )
    (net (code "158") (name "unconnected-(U5-SW-Pad3)") (class "Default")
      (node (ref "U5") (pin "3") (pinfunction "SW_3") (pintype "unspecified"))
    )
    (net (code "159") (name "unconnected-(U7-5C-Pad12)") (class "Default")
      (node (ref "U7") (pin "12") (pinfunction "5C_12") (pintype "unspecified"))
    )
    (net (code "160") (name "unconnected-(U7-6C-Pad11)") (class "Default")
      (node (ref "U7") (pin "11") (pinfunction "6C_11") (pintype "unspecified"))
    )
    (net (code "161") (name "unconnected-(U7-7C-Pad10)") (class "Default")
      (node (ref "U7") (pin "10") (pinfunction "7C_10") (pintype "unspecified"))
    )
    (net (code "162") (name "unconnected-(U7-COM-Pad9)") (class "Default")
      (node (ref "U7") (pin "9") (pinfunction "COM_9") (pintype "unspecified"))
    )
    (net (code "163") (name "unconnected-(U8-QH-Pad7)") (class "Default")
      (node (ref "U8") (pin "7") (pinfunction "QH_7") (pintype "unspecified"))
    )
    (net (code "164") (name "unconnected-(U8-SDO-Pad9)") (class "Default")
      (node (ref "U8") (pin "9") (pinfunction "SDO_9") (pintype "output"))
    )
    (net (code "165") (name "unconnected-(U9-A4-Pad1)") (class "Default")
      (node (ref "U9") (pin "1") (pinfunction "A4_1") (pintype "unspecified"))
    )
    (net (code "166") (name "unconnected-(U9-A5-Pad5)") (class "Default")
      (node (ref "U9") (pin "5") (pinfunction "A5_5") (pintype "unspecified"))
    )
    (net (code "167") (name "unconnected-(U9-A6-Pad2)") (class "Default")
      (node (ref "U9") (pin "2") (pinfunction "A6_2") (pintype "unspecified"))
    )
    (net (code "168") (name "unconnected-(U9-A7-Pad4)") (class "Default")
      (node (ref "U9") (pin "4") (pinfunction "A7_4") (pintype "unspecified"))
    )
    (net (code "169") (name "unconnected-(U9-E#-Pad6)") (class "Default")
      (node (ref "U9") (pin "6") (pinfunction "E#_6") (pintype "unspecified"))
    )
    (net (code "170") (name "unconnected-(U10-QH-Pad7)") (class "Default")
      (node (ref "U10") (pin "7") (pinfunction "QH_7") (pintype "unspecified"))
    )
    (net (code "171") (name "unconnected-(U10-SDO-Pad9)") (class "Default")
      (node (ref "U10") (pin "9") (pinfunction "SDO_9") (pintype "output"))
    )
    (net (code "172") (name "unconnected-(U11-4C-Pad13)") (class "Default")
      (node (ref "U11") (pin "13") (pinfunction "4C_13") (pintype "unspecified"))
    )
    (net (code "173") (name "unconnected-(U11-5C-Pad12)") (class "Default")
      (node (ref "U11") (pin "12") (pinfunction "5C_12") (pintype "unspecified"))
    )
    (net (code "174") (name "unconnected-(U11-6C-Pad11)") (class "Default")
      (node (ref "U11") (pin "11") (pinfunction "6C_11") (pintype "unspecified"))
    )
    (net (code "175") (name "unconnected-(U11-7C-Pad10)") (class "Default")
      (node (ref "U11") (pin "10") (pinfunction "7C_10") (pintype "unspecified"))
    )
    (net (code "176") (name "unconnected-(U11-COM-Pad9)") (class "Default")
      (node (ref "U11") (pin "9") (pinfunction "COM_9") (pintype "unspecified"))
    )
    (net (code "177") (name "unconnected-(U12-3C-Pad14)") (class "Default")
      (node (ref "U12") (pin "14") (pinfunction "3C_14") (pintype "unspecified"))
    )
    (net (code "178") (name "unconnected-(U12-4C-Pad13)") (class "Default")
      (node (ref "U12") (pin "13") (pinfunction "4C_13") (pintype "unspecified"))
    )
    (net (code "179") (name "unconnected-(U12-5C-Pad12)") (class "Default")
      (node (ref "U12") (pin "12") (pinfunction "5C_12") (pintype "unspecified"))
    )
    (net (code "180") (name "unconnected-(U12-6C-Pad11)") (class "Default")
      (node (ref "U12") (pin "11") (pinfunction "6C_11") (pintype "unspecified"))
    )
    (net (code "181") (name "unconnected-(U12-7C-Pad10)") (class "Default")
      (node (ref "U12") (pin "10") (pinfunction "7C_10") (pintype "unspecified"))
    )
    (net (code "182") (name "unconnected-(U12-COM-Pad9)") (class "Default")
      (node (ref "U12") (pin "9") (pinfunction "COM_9") (pintype "unspecified"))
    )
    (net (code "183") (name "unconnected-(U13-QH-Pad7)") (class "Default")
      (node (ref "U13") (pin "7") (pinfunction "QH_7") (pintype "unspecified"))
    )
    (net (code "184") (name "unconnected-(U13-SDO-Pad9)") (class "Default")
      (node (ref "U13") (pin "9") (pinfunction "SDO_9") (pintype "output"))
    )
    (net (code "185") (name "unconnected-(U14-A4-Pad1)") (class "Default")
      (node (ref "U14") (pin "1") (pinfunction "A4_1") (pintype "unspecified"))
    )
    (net (code "186") (name "unconnected-(U14-A5-Pad5)") (class "Default")
      (node (ref "U14") (pin "5") (pinfunction "A5_5") (pintype "unspecified"))
    )
    (net (code "187") (name "unconnected-(U14-A6-Pad2)") (class "Default")
      (node (ref "U14") (pin "2") (pinfunction "A6_2") (pintype "unspecified"))
    )
    (net (code "188") (name "unconnected-(U14-A7-Pad4)") (class "Default")
      (node (ref "U14") (pin "4") (pinfunction "A7_4") (pintype "unspecified"))
    )
    (net (code "189") (name "unconnected-(U14-E#-Pad6)") (class "Default")
      (node (ref "U14") (pin "6") (pinfunction "E#_6") (pintype "unspecified"))
    )
  )
)
